# air_qual_mqtt.net
KiCad netlist of a schematic drawn in EAGLE
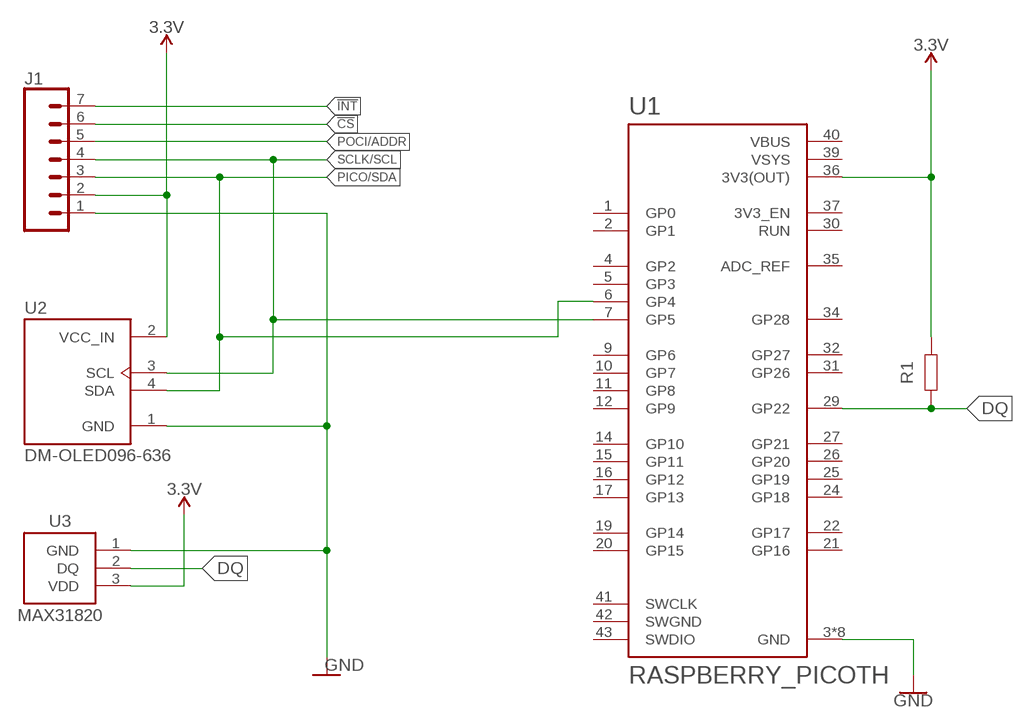
[diagram p0: schematic, sheet 1]

(export (version "E")
  (design (tool "Eeschema 10.0.6"))
  (components
    (comp (ref "J1")
      (value "CONN_07NO_SILK")
      (footprint "eagle-import:1X07_NO_SILK")
      (libsource (lib "eagle-import") (part "CONN_07NO_SILK"))
    )
    (comp (ref "R1")
      (value "R_AXIAL-11.7MM-PITCH")
      (footprint "eagle-import:RESAD1176W63L850D250B")
      (libsource (lib "eagle-import") (part "RAXIAL-11.7MM-PITCH_"))
    )
    (comp (ref "U1")
      (value "RASPBERRY_PICOTH")
      (footprint "eagle-import:PICO-PKG-TH")
      (libsource (lib "eagle-import") (part "RASPBERRY_PICOTH"))
    )
    (comp (ref "U2")
      (value "DM-OLED096-636")
      (footprint "eagle-import:MODULE_DM-OLED096-636")
      (fields (field (name "MF") "Display Module"))
      (libsource (lib "eagle-import") (part "DM-OLED096-636"))
    )
    (comp (ref "U3")
      (value "MAX31820")
      (footprint "eagle-import:TO92")
      (libsource (lib "eagle-import") (part "MAX31820"))
    )
  )
  (nets
    (net (code "1") (name "/SWGND") (class "Default")
      (node (ref "U1") (pin "42") (pinfunction "SWGND_42") (pintype "power_in"))
    )
    (net (code "2") (name "/VBUS") (class "Default")
      (node (ref "U1") (pin "40") (pinfunction "VBUS_40") (pintype "power_in"))
    )
    (net (code "3") (name "/VSYS") (class "Default")
      (node (ref "U1") (pin "39") (pinfunction "VSYS_39") (pintype "power_in"))
    )
    (net (code "4") (name "/~{CS}") (class "Default")
      (node (ref "J1") (pin "6") (pinfunction "6_6") (pintype "passive"))
    )
    (net (code "5") (name "/~{INT}") (class "Default")
      (node (ref "J1") (pin "7") (pinfunction "7_7") (pintype "passive"))
    )
    (net (code "6") (name "3.3V") (class "Default")
      (node (ref "J1") (pin "2") (pinfunction "2_2") (pintype "passive"))
      (node (ref "R1") (pin "2") (pinfunction "2_2") (pintype "passive"))
      (node (ref "U1") (pin "36") (pinfunction "3V3(OUT)_36") (pintype "power_in"))
      (node (ref "U2") (pin "2") (pinfunction "VCC_IN_2") (pintype "power_in"))
      (node (ref "U3") (pin "3") (pinfunction "VDD_3") (pintype "power_in"))
    )
    (net (code "7") (name "DQ") (class "Default")
      (node (ref "R1") (pin "1") (pinfunction "1_1") (pintype "passive"))
      (node (ref "U1") (pin "29") (pinfunction "GP22_29") (pintype "bidirectional"))
      (node (ref "U3") (pin "2") (pinfunction "DQ_2") (pintype "bidirectional"))
    )
    (net (code "8") (name "GND") (class "Default")
      (node (ref "J1") (pin "1") (pinfunction "1_1") (pintype "passive"))
      (node (ref "U1") (pin "13") (pinfunction "GND_13") (pintype "power_in"))
      (node (ref "U1") (pin "18") (pinfunction "GND_18") (pintype "power_in"))
      (node (ref "U1") (pin "23") (pinfunction "GND_23") (pintype "power_in"))
      (node (ref "U1") (pin "28") (pinfunction "GND_28") (pintype "power_in"))
      (node (ref "U1") (pin "3") (pinfunction "GND_3") (pintype "power_in"))
      (node (ref "U1") (pin "33") (pinfunction "GND_33") (pintype "power_in"))
      (node (ref "U1") (pin "38") (pinfunction "GND_38") (pintype "power_in"))
      (node (ref "U1") (pin "8") (pinfunction "GND_8") (pintype "power_in"))
      (node (ref "U2") (pin "1") (pinfunction "GND_1") (pintype "power_in"))
      (node (ref "U3") (pin "1") (pinfunction "GND_1") (pintype "power_in"))
    )
    (net (code "9") (name "PICO{slash}SDA") (class "Default")
      (node (ref "J1") (pin "3") (pinfunction "3_3") (pintype "passive"))
      (node (ref "U1") (pin "6") (pinfunction "GP4_6") (pintype "bidirectional"))
      (node (ref "U2") (pin "4") (pinfunction "SDA_4") (pintype "bidirectional"))
    )
    (net (code "10") (name "POCI{slash}ADDR") (class "Default")
      (node (ref "J1") (pin "5") (pinfunction "5_5") (pintype "passive"))
    )
    (net (code "11") (name "SCLK{slash}SCL") (class "Default")
      (node (ref "J1") (pin "4") (pinfunction "4_4") (pintype "passive"))
      (node (ref "U1") (pin "7") (pinfunction "GP5_7") (pintype "bidirectional"))
      (node (ref "U2") (pin "3") (pinfunction "SCL_3") (pintype "input"))
    )
    (net (code "12") (name "unconnected-(U1-3V3_EN-Pad37)") (class "Default")
      (node (ref "U1") (pin "37") (pinfunction "3V3_EN_37") (pintype "input"))
    )
    (net (code "13") (name "unconnected-(U1-ADC_REF-Pad35)") (class "Default")
      (node (ref "U1") (pin "35") (pinfunction "ADC_REF_35") (pintype "input"))
    )
    (net (code "14") (name "unconnected-(U1-GP0-Pad1)") (class "Default")
      (node (ref "U1") (pin "1") (pinfunction "GP0_1") (pintype "bidirectional"))
    )
    (net (code "15") (name "unconnected-(U1-GP1-Pad2)") (class "Default")
      (node (ref "U1") (pin "2") (pinfunction "GP1_2") (pintype "bidirectional"))
    )
    (net (code "16") (name "unconnected-(U1-GP2-Pad4)") (class "Default")
      (node (ref "U1") (pin "4") (pinfunction "GP2_4") (pintype "bidirectional"))
    )
    (net (code "17") (name "unconnected-(U1-GP3-Pad5)") (class "Default")
      (node (ref "U1") (pin "5") (pinfunction "GP3_5") (pintype "bidirectional"))
    )
    (net (code "18") (name "unconnected-(U1-GP6-Pad9)") (class "Default")
      (node (ref "U1") (pin "9") (pinfunction "GP6_9") (pintype "bidirectional"))
    )
    (net (code "19") (name "unconnected-(U1-GP7-Pad10)") (class "Default")
      (node (ref "U1") (pin "10") (pinfunction "GP7_10") (pintype "bidirectional"))
    )
    (net (code "20") (name "unconnected-(U1-GP8-Pad11)") (class "Default")
      (node (ref "U1") (pin "11") (pinfunction "GP8_11") (pintype "bidirectional"))
    )
    (net (code "21") (name "unconnected-(U1-GP9-Pad12)") (class "Default")
      (node (ref "U1") (pin "12") (pinfunction "GP9_12") (pintype "bidirectional"))
    )
    (net (code "22") (name "unconnected-(U1-GP10-Pad14)") (class "Default")
      (node (ref "U1") (pin "14") (pinfunction "GP10_14") (pintype "bidirectional"))
    )
    (net (code "23") (name "unconnected-(U1-GP11-Pad15)") (class "Default")
      (node (ref "U1") (pin "15") (pinfunction "GP11_15") (pintype "bidirectional"))
    )
    (net (code "24") (name "unconnected-(U1-GP12-Pad16)") (class "Default")
      (node (ref "U1") (pin "16") (pinfunction "GP12_16") (pintype "bidirectional"))
    )
    (net (code "25") (name "unconnected-(U1-GP13-Pad17)") (class "Default")
      (node (ref "U1") (pin "17") (pinfunction "GP13_17") (pintype "bidirectional"))
    )
    (net (code "26") (name "unconnected-(U1-GP14-Pad19)") (class "Default")
      (node (ref "U1") (pin "19") (pinfunction "GP14_19") (pintype "bidirectional"))
    )
    (net (code "27") (name "unconnected-(U1-GP15-Pad20)") (class "Default")
      (node (ref "U1") (pin "20") (pinfunction "GP15_20") (pintype "bidirectional"))
    )
    (net (code "28") (name "unconnected-(U1-GP16-Pad21)") (class "Default")
      (node (ref "U1") (pin "21") (pinfunction "GP16_21") (pintype "bidirectional"))
    )
    (net (code "29") (name "unconnected-(U1-GP17-Pad22)") (class "Default")
      (node (ref "U1") (pin "22") (pinfunction "GP17_22") (pintype "bidirectional"))
    )
    (net (code "30") (name "unconnected-(U1-GP18-Pad24)") (class "Default")
      (node (ref "U1") (pin "24") (pinfunction "GP18_24") (pintype "bidirectional"))
    )
    (net (code "31") (name "unconnected-(U1-GP19-Pad25)") (class "Default")
      (node (ref "U1") (pin "25") (pinfunction "GP19_25") (pintype "bidirectional"))
    )
    (net (code "32") (name "unconnected-(U1-GP20-Pad26)") (class "Default")
      (node (ref "U1") (pin "26") (pinfunction "GP20_26") (pintype "bidirectional"))
    )
    (net (code "33") (name "unconnected-(U1-GP21-Pad27)") (class "Default")
      (node (ref "U1") (pin "27") (pinfunction "GP21_27") (pintype "bidirectional"))
    )
    (net (code "34") (name "unconnected-(U1-GP26-Pad31)") (class "Default")
      (node (ref "U1") (pin "31") (pinfunction "GP26_31") (pintype "bidirectional"))
    )
    (net (code "35") (name "unconnected-(U1-GP27-Pad32)") (class "Default")
      (node (ref "U1") (pin "32") (pinfunction "GP27_32") (pintype "bidirectional"))
    )
    (net (code "36") (name "unconnected-(U1-GP28-Pad34)") (class "Default")
      (node (ref "U1") (pin "34") (pinfunction "GP28_34") (pintype "bidirectional"))
    )
    (net (code "37") (name "unconnected-(U1-RUN-Pad30)") (class "Default")
      (node (ref "U1") (pin "30") (pinfunction "RUN_30") (pintype "input"))
    )
    (net (code "38") (name "unconnected-(U1-SWCLK-Pad41)") (class "Default")
      (node (ref "U1") (pin "41") (pinfunction "SWCLK_41") (pintype "input"))
    )
    (net (code "39") (name "unconnected-(U1-SWDIO-Pad43)") (class "Default")
      (node (ref "U1") (pin "43") (pinfunction "SWDIO_43") (pintype "bidirectional"))
    )
  )
)
